# Solid_Sequencer.net
KiCad netlist of a schematic drawn in EAGLE
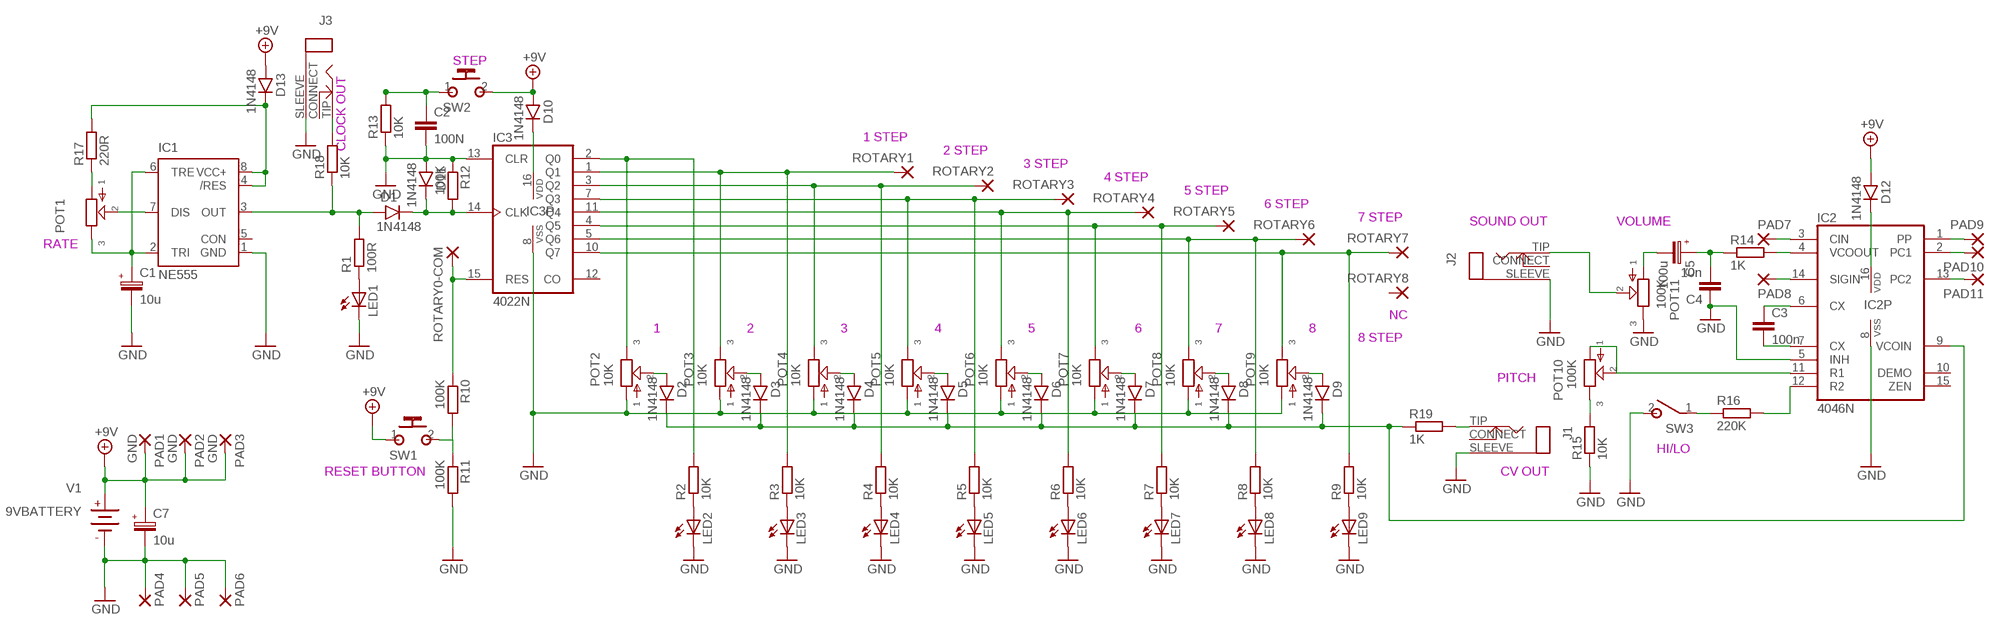
[diagram p0: schematic, sheet 1]

(export (version "E")
  (design (tool "Eeschema 10.0.6"))
  (components
    (comp (ref "C1")
      (value "10u")
      (footprint "eagle-import:050_020")
      (libsource (lib "eagle-import") (part "050-EU"))
    )
    (comp (ref "C2")
      (value "100N")
      (footprint "eagle-import:075X030_3")
      (libsource (lib "eagle-import") (part "075X0303"))
    )
    (comp (ref "C3")
      (value "100n")
      (footprint "eagle-import:075X030")
      (libsource (lib "eagle-import") (part "075X0302"))
    )
    (comp (ref "C4")
      (value "10n")
      (footprint "eagle-import:075X030")
      (libsource (lib "eagle-import") (part "075X0302"))
    )
    (comp (ref "C5")
      (value "100u")
      (footprint "eagle-import:050_020_1")
      (libsource (lib "eagle-import") (part "050-EU1"))
    )
    (comp (ref "C7")
      (value "10u")
      (footprint "eagle-import:050_020_1")
      (libsource (lib "eagle-import") (part "050-EU1"))
    )
    (comp (ref "D1")
      (value "1N4148")
      (footprint "eagle-import:DO35-3")
      (libsource (lib "eagle-import") (part "1N914.3"))
    )
    (comp (ref "D2")
      (value "1N4148")
      (footprint "eagle-import:DO35-3")
      (libsource (lib "eagle-import") (part "1N914.3"))
    )
    (comp (ref "D3")
      (value "1N4148")
      (footprint "eagle-import:DO35-3")
      (libsource (lib "eagle-import") (part "1N914.3"))
    )
    (comp (ref "D4")
      (value "1N4148")
      (footprint "eagle-import:DO35-3")
      (libsource (lib "eagle-import") (part "1N914.3"))
    )
    (comp (ref "D5")
      (value "1N4148")
      (footprint "eagle-import:DO35-3")
      (libsource (lib "eagle-import") (part "1N914.3"))
    )
    (comp (ref "D6")
      (value "1N4148")
      (footprint "eagle-import:DO35-3")
      (libsource (lib "eagle-import") (part "1N914.3"))
    )
    (comp (ref "D7")
      (value "1N4148")
      (footprint "eagle-import:DO35-3")
      (libsource (lib "eagle-import") (part "1N914.3"))
    )
    (comp (ref "D8")
      (value "1N4148")
      (footprint "eagle-import:DO35-3")
      (libsource (lib "eagle-import") (part "1N914.3"))
    )
    (comp (ref "D9")
      (value "1N4148")
      (footprint "eagle-import:DO35-3")
      (libsource (lib "eagle-import") (part "1N914.3"))
    )
    (comp (ref "D10")
      (value "1N4148")
      (footprint "eagle-import:DO35-3")
      (libsource (lib "eagle-import") (part "1N914.3"))
    )
    (comp (ref "D11")
      (value "1N4148")
      (footprint "eagle-import:DO35-3")
      (libsource (lib "eagle-import") (part "1N914.3"))
    )
    (comp (ref "D12")
      (value "1N4148")
      (footprint "eagle-import:DO35-3")
      (libsource (lib "eagle-import") (part "1N914.3"))
    )
    (comp (ref "D13")
      (value "1N4148")
      (footprint "eagle-import:DO35-3")
      (libsource (lib "eagle-import") (part "1N914.3"))
    )
    (comp (ref "IC1")
      (value "NE555")
      (footprint "eagle-import:DIL-08")
      (fields (field (name "MF") "Arrow Electronics") (field (name "MPN") "NE555N"))
      (libsource (lib "eagle-import") (part "NE555"))
    )
    (comp (ref "IC2")
      (value "4046N")
      (footprint "eagle-import:DIL16")
      (libsource (lib "eagle-import") (part "4046N"))
    )
    (comp (ref "IC3")
      (value "4022N")
      (footprint "eagle-import:DIL16")
      (libsource (lib "eagle-import") (part "4022N"))
    )
    (comp (ref "J1")
      (value "CLOSEDMONO")
      (footprint "eagle-import:CLOSED_MONO_JACK")
      (libsource (lib "eagle-import") (part "CLOSEDMONO"))
    )
    (comp (ref "J2")
      (value "CLOSEDMONO")
      (footprint "eagle-import:CLOSED_MONO_JACK")
      (libsource (lib "eagle-import") (part "CLOSEDMONO"))
    )
    (comp (ref "J3")
      (value "CLOSEDMONO")
      (footprint "eagle-import:CLOSED_MONO_JACK")
      (libsource (lib "eagle-import") (part "CLOSEDMONO"))
    )
    (comp (ref "LED1")
      (value "LED3MM")
      (footprint "eagle-import:LED3MM")
      (libsource (lib "eagle-import") (part "LED3MM"))
    )
    (comp (ref "LED2")
      (value "LED3MM")
      (footprint "eagle-import:LED3MM")
      (libsource (lib "eagle-import") (part "LED3MM"))
    )
    (comp (ref "LED3")
      (value "LED3MM")
      (footprint "eagle-import:LED3MM")
      (libsource (lib "eagle-import") (part "LED3MM"))
    )
    (comp (ref "LED4")
      (value "LED3MM")
      (footprint "eagle-import:LED3MM")
      (libsource (lib "eagle-import") (part "LED3MM"))
    )
    (comp (ref "LED5")
      (value "LED3MM")
      (footprint "eagle-import:LED3MM")
      (libsource (lib "eagle-import") (part "LED3MM"))
    )
    (comp (ref "LED6")
      (value "LED3MM")
      (footprint "eagle-import:LED3MM")
      (libsource (lib "eagle-import") (part "LED3MM"))
    )
    (comp (ref "LED7")
      (value "LED3MM")
      (footprint "eagle-import:LED3MM")
      (libsource (lib "eagle-import") (part "LED3MM"))
    )
    (comp (ref "LED8")
      (value "LED3MM")
      (footprint "eagle-import:LED3MM")
      (libsource (lib "eagle-import") (part "LED3MM"))
    )
    (comp (ref "LED9")
      (value "LED3MM")
      (footprint "eagle-import:LED3MM")
      (libsource (lib "eagle-import") (part "LED3MM"))
    )
    (comp (ref "PAD1")
      (value "GND")
      (footprint "eagle-import:2,15_1,0")
      (libsource (lib "eagle-import") (part "2,15/1,0"))
    )
    (comp (ref "PAD2")
      (value "GND")
      (footprint "eagle-import:2,15_1,0")
      (libsource (lib "eagle-import") (part "2,15/1,0"))
    )
    (comp (ref "PAD3")
      (value "GND")
      (footprint "eagle-import:2,15_1,0")
      (libsource (lib "eagle-import") (part "2,15/1,0"))
    )
    (comp (ref "PAD4")
      (value "2,15/1,0")
      (footprint "eagle-import:2,15_1,0")
      (libsource (lib "eagle-import") (part "2,15/1,0"))
    )
    (comp (ref "PAD5")
      (value "2,15/1,0")
      (footprint "eagle-import:2,15_1,0")
      (libsource (lib "eagle-import") (part "2,15/1,0"))
    )
    (comp (ref "PAD6")
      (value "2,15/1,0")
      (footprint "eagle-import:2,15_1,0")
      (libsource (lib "eagle-import") (part "2,15/1,0"))
    )
    (comp (ref "PAD7")
      (value "2,15/1,0")
      (footprint "eagle-import:2,15_1,0")
      (libsource (lib "eagle-import") (part "2,15/1,0"))
    )
    (comp (ref "PAD8")
      (value "2,15/1,0")
      (footprint "eagle-import:2,15_1,0")
      (libsource (lib "eagle-import") (part "2,15/1,0"))
    )
    (comp (ref "PAD9")
      (value "2,15/1,0")
      (footprint "eagle-import:2,15_1,0")
      (libsource (lib "eagle-import") (part "2,15/1,0"))
    )
    (comp (ref "PAD10")
      (value "2,15/1,0")
      (footprint "eagle-import:2,15_1,0")
      (libsource (lib "eagle-import") (part "2,15/1,0"))
    )
    (comp (ref "PAD11")
      (value "2,15/1,0")
      (footprint "eagle-import:2,15_1,0")
      (libsource (lib "eagle-import") (part "2,15/1,0"))
    )
    (comp (ref "POT1")
      (value "POT-EU")
      (footprint "eagle-import:POT")
      (libsource (lib "eagle-import") (part "POT-EU"))
    )
    (comp (ref "POT2")
      (value "10K")
      (footprint "eagle-import:POT")
      (libsource (lib "eagle-import") (part "POT-EU"))
    )
    (comp (ref "POT3")
      (value "10K")
      (footprint "eagle-import:POT")
      (libsource (lib "eagle-import") (part "POT-EU"))
    )
    (comp (ref "POT4")
      (value "10K")
      (footprint "eagle-import:POT")
      (libsource (lib "eagle-import") (part "POT-EU"))
    )
    (comp (ref "POT5")
      (value "10K")
      (footprint "eagle-import:POT")
      (libsource (lib "eagle-import") (part "POT-EU"))
    )
    (comp (ref "POT6")
      (value "10K")
      (footprint "eagle-import:POT")
      (libsource (lib "eagle-import") (part "POT-EU"))
    )
    (comp (ref "POT7")
      (value "10K")
      (footprint "eagle-import:POT")
      (libsource (lib "eagle-import") (part "POT-EU"))
    )
    (comp (ref "POT8")
      (value "10K")
      (footprint "eagle-import:POT")
      (libsource (lib "eagle-import") (part "POT-EU"))
    )
    (comp (ref "POT9")
      (value "10K")
      (footprint "eagle-import:POT")
      (libsource (lib "eagle-import") (part "POT-EU"))
    )
    (comp (ref "POT10")
      (value "100K")
      (footprint "eagle-import:POT")
      (libsource (lib "eagle-import") (part "POT-EU"))
    )
    (comp (ref "POT11")
      (value "100K")
      (footprint "eagle-import:POT")
      (libsource (lib "eagle-import") (part "POT-EU"))
    )
    (comp (ref "R1")
      (value "100R")
      (footprint "eagle-import:0207_7")
      (libsource (lib "eagle-import") (part "R-EU_0207/7"))
    )
    (comp (ref "R2")
      (value "10K")
      (footprint "eagle-import:0207_7")
      (libsource (lib "eagle-import") (part "R-EU_0207/7"))
    )
    (comp (ref "R3")
      (value "10K")
      (footprint "eagle-import:0207_7")
      (libsource (lib "eagle-import") (part "R-EU_0207/7"))
    )
    (comp (ref "R4")
      (value "10K")
      (footprint "eagle-import:0207_7")
      (libsource (lib "eagle-import") (part "R-EU_0207/7"))
    )
    (comp (ref "R5")
      (value "10K")
      (footprint "eagle-import:0207_7")
      (libsource (lib "eagle-import") (part "R-EU_0207/7"))
    )
    (comp (ref "R6")
      (value "10K")
      (footprint "eagle-import:0207_7")
      (libsource (lib "eagle-import") (part "R-EU_0207/7"))
    )
    (comp (ref "R7")
      (value "10K")
      (footprint "eagle-import:0207_7")
      (libsource (lib "eagle-import") (part "R-EU_0207/7"))
    )
    (comp (ref "R8")
      (value "10K")
      (footprint "eagle-import:0207_7")
      (libsource (lib "eagle-import") (part "R-EU_0207/7"))
    )
    (comp (ref "R9")
      (value "10K")
      (footprint "eagle-import:0207_7")
      (libsource (lib "eagle-import") (part "R-EU_0207/7"))
    )
    (comp (ref "R10")
      (value "100K")
      (footprint "eagle-import:0207_7")
      (libsource (lib "eagle-import") (part "R-EU_0207/7"))
    )
    (comp (ref "R11")
      (value "100K")
      (footprint "eagle-import:0207_7")
      (libsource (lib "eagle-import") (part "R-EU_0207/7"))
    )
    (comp (ref "R12")
      (value "100K")
      (footprint "eagle-import:0207_7")
      (libsource (lib "eagle-import") (part "R-EU_0207/7"))
    )
    (comp (ref "R13")
      (value "10K")
      (footprint "eagle-import:0207_7")
      (libsource (lib "eagle-import") (part "R-EU_0207/7"))
    )
    (comp (ref "R14")
      (value "1K")
      (footprint "eagle-import:0207_7")
      (libsource (lib "eagle-import") (part "R-EU_0207/7"))
    )
    (comp (ref "R15")
      (value "10K")
      (footprint "eagle-import:0207_7")
      (libsource (lib "eagle-import") (part "R-EU_0207/7"))
    )
    (comp (ref "R16")
      (value "220K")
      (footprint "eagle-import:0207_7")
      (libsource (lib "eagle-import") (part "R-EU_0207/7"))
    )
    (comp (ref "R17")
      (value "220R")
      (footprint "eagle-import:0207_7")
      (libsource (lib "eagle-import") (part "R-EU_0207/7"))
    )
    (comp (ref "R18")
      (value "10K")
      (footprint "eagle-import:0207_7")
      (libsource (lib "eagle-import") (part "R-EU_0207/7"))
    )
    (comp (ref "R19")
      (value "1K")
      (footprint "eagle-import:0207_7")
      (libsource (lib "eagle-import") (part "R-EU_0207/7"))
    )
    (comp (ref "ROTARY0-COM")
      (value "2,15/1,0")
      (footprint "eagle-import:2,15_1,0")
      (libsource (lib "eagle-import") (part "2,15/1,0"))
    )
    (comp (ref "ROTARY1")
      (value "2,15/1,0")
      (footprint "eagle-import:2,15_1,0")
      (libsource (lib "eagle-import") (part "2,15/1,0"))
    )
    (comp (ref "ROTARY2")
      (value "2,15/1,0")
      (footprint "eagle-import:2,15_1,0")
      (libsource (lib "eagle-import") (part "2,15/1,0"))
    )
    (comp (ref "ROTARY3")
      (value "2,15/1,0")
      (footprint "eagle-import:2,15_1,0")
      (libsource (lib "eagle-import") (part "2,15/1,0"))
    )
    (comp (ref "ROTARY4")
      (value "2,15/1,0")
      (footprint "eagle-import:2,15_1,0")
      (libsource (lib "eagle-import") (part "2,15/1,0"))
    )
    (comp (ref "ROTARY5")
      (value "2,15/1,0")
      (footprint "eagle-import:2,15_1,0")
      (libsource (lib "eagle-import") (part "2,15/1,0"))
    )
    (comp (ref "ROTARY6")
      (value "2,15/1,0")
      (footprint "eagle-import:2,15_1,0")
      (libsource (lib "eagle-import") (part "2,15/1,0"))
    )
    (comp (ref "ROTARY7")
      (value "2,15/1,0")
      (footprint "eagle-import:2,15_1,0")
      (libsource (lib "eagle-import") (part "2,15/1,0"))
    )
    (comp (ref "ROTARY8")
      (value "2,15/1,0")
      (footprint "eagle-import:2,15_1,0")
      (libsource (lib "eagle-import") (part "2,15/1,0"))
    )
    (comp (ref "SW1")
      (value "MOMENTARY")
      (footprint "eagle-import:SPST")
      (libsource (lib "eagle-import") (part "MOMENTARY"))
    )
    (comp (ref "SW2")
      (value "MOMENTARY")
      (footprint "eagle-import:SPST")
      (libsource (lib "eagle-import") (part "MOMENTARY"))
    )
    (comp (ref "SW3")
      (value "SPST")
      (footprint "eagle-import:SPST")
      (libsource (lib "eagle-import") (part "SPST"))
    )
    (comp (ref "V1")
      (value "9VBATTERY")
      (footprint "eagle-import:AB9V")
      (libsource (lib "eagle-import") (part "9VBATTERY"))
    )
  )
  (nets
    (net (code "1") (name "+9V") (class "Default")
      (node (ref "C7") (pin "+") (pinfunction "+_+") (pintype "passive"))
      (node (ref "D10") (pin "A") (pinfunction "A_A") (pintype "passive"))
      (node (ref "D12") (pin "A") (pinfunction "A_A") (pintype "passive"))
      (node (ref "D13") (pin "A") (pinfunction "A_A") (pintype "passive"))
      (node (ref "PAD1") (pin "1") (pinfunction "P_1") (pintype "passive"))
      (node (ref "PAD2") (pin "1") (pinfunction "P_1") (pintype "passive"))
      (node (ref "PAD3") (pin "1") (pinfunction "P_1") (pintype "passive"))
      (node (ref "SW1") (pin "1") (pinfunction "P_1") (pintype "passive"))
      (node (ref "SW2") (pin "2") (pinfunction "S_2") (pintype "passive"))
      (node (ref "V1") (pin "+") (pinfunction "+_+") (pintype "passive"))
    )
    (net (code "2") (name "GND") (class "Default")
      (node (ref "C1") (pin "-") (pinfunction "-_-") (pintype "passive"))
      (node (ref "C2") (pin "2") (pinfunction "2_2") (pintype "passive"))
      (node (ref "C4") (pin "1") (pinfunction "1_1") (pintype "passive"))
      (node (ref "C7") (pin "-") (pinfunction "-_-") (pintype "passive"))
      (node (ref "D11") (pin "A") (pinfunction "A_A") (pintype "passive"))
      (node (ref "IC1") (pin "1") (pinfunction "GND_1") (pintype "power_in"))
      (node (ref "IC2") (pin "5") (pinfunction "INH_5") (pintype "input"))
      (node (ref "IC2") (pin "8") (pinfunction "VSS_8") (pintype "power_in"))
      (node (ref "IC3") (pin "13") (pinfunction "CLR_13") (pintype "input"))
      (node (ref "IC3") (pin "8") (pinfunction "VSS_8") (pintype "power_in"))
      (node (ref "J1") (pin "SLEEVE") (pinfunction "RING_SLEEVE") (pintype "passive"))
      (node (ref "J2") (pin "SLEEVE") (pinfunction "RING_SLEEVE") (pintype "passive"))
      (node (ref "J3") (pin "SLEEVE") (pinfunction "RING_SLEEVE") (pintype "passive"))
      (node (ref "LED1") (pin "K") (pinfunction "C_K") (pintype "passive"))
      (node (ref "LED2") (pin "K") (pinfunction "C_K") (pintype "passive"))
      (node (ref "LED3") (pin "K") (pinfunction "C_K") (pintype "passive"))
      (node (ref "LED4") (pin "K") (pinfunction "C_K") (pintype "passive"))
      (node (ref "LED5") (pin "K") (pinfunction "C_K") (pintype "passive"))
      (node (ref "LED6") (pin "K") (pinfunction "C_K") (pintype "passive"))
      (node (ref "LED7") (pin "K") (pinfunction "C_K") (pintype "passive"))
      (node (ref "LED8") (pin "K") (pinfunction "C_K") (pintype "passive"))
      (node (ref "LED9") (pin "K") (pinfunction "C_K") (pintype "passive"))
      (node (ref "PAD4") (pin "1") (pinfunction "P_1") (pintype "passive"))
      (node (ref "PAD5") (pin "1") (pinfunction "P_1") (pintype "passive"))
      (node (ref "PAD6") (pin "1") (pinfunction "P_1") (pintype "passive"))
      (node (ref "POT11") (pin "3") (pinfunction "3_3") (pintype "passive"))
      (node (ref "POT2") (pin "1") (pinfunction "1_1") (pintype "passive"))
      (node (ref "POT3") (pin "1") (pinfunction "1_1") (pintype "passive"))
      (node (ref "POT4") (pin "1") (pinfunction "1_1") (pintype "passive"))
      (node (ref "POT5") (pin "1") (pinfunction "1_1") (pintype "passive"))
      (node (ref "POT6") (pin "1") (pinfunction "1_1") (pintype "passive"))
      (node (ref "POT7") (pin "1") (pinfunction "1_1") (pintype "passive"))
      (node (ref "POT8") (pin "1") (pinfunction "1_1") (pintype "passive"))
      (node (ref "POT9") (pin "1") (pinfunction "1_1") (pintype "passive"))
      (node (ref "R11") (pin "2") (pinfunction "2_2") (pintype "passive"))
      (node (ref "R12") (pin "1") (pinfunction "1_1") (pintype "passive"))
      (node (ref "R13") (pin "1") (pinfunction "1_1") (pintype "passive"))
      (node (ref "R15") (pin "1") (pinfunction "1_1") (pintype "passive"))
      (node (ref "SW3") (pin "2") (pinfunction "S_2") (pintype "passive"))
      (node (ref "V1") (pin "-") (pinfunction "-_-") (pintype "passive"))
    )
    (net (code "3") (name "Net-(C3-Pad1)") (class "Default")
      (node (ref "C3") (pin "1") (pinfunction "1_1") (pintype "passive"))
      (node (ref "IC2") (pin "6") (pinfunction "CX_6") (pintype "input"))
    )
    (net (code "4") (name "Net-(C3-Pad2)") (class "Default")
      (node (ref "C3") (pin "2") (pinfunction "2_2") (pintype "passive"))
      (node (ref "IC2") (pin "7") (pinfunction "CX_7") (pintype "input"))
    )
    (net (code "5") (name "Net-(C4-Pad2)") (class "Default")
      (node (ref "C4") (pin "2") (pinfunction "2_2") (pintype "passive"))
      (node (ref "C5") (pin "+") (pinfunction "+_+") (pintype "passive"))
      (node (ref "R14") (pin "1") (pinfunction "1_1") (pintype "passive"))
    )
    (net (code "6") (name "Net-(C5-Pad-)") (class "Default")
      (node (ref "C5") (pin "-") (pinfunction "-_-") (pintype "passive"))
      (node (ref "POT11") (pin "1") (pinfunction "1_1") (pintype "passive"))
    )
    (net (code "7") (name "Net-(D2-PadA)") (class "Default")
      (node (ref "D2") (pin "A") (pinfunction "A_A") (pintype "passive"))
      (node (ref "POT2") (pin "2") (pinfunction "2_2") (pintype "passive"))
    )
    (net (code "8") (name "Net-(D3-PadA)") (class "Default")
      (node (ref "D3") (pin "A") (pinfunction "A_A") (pintype "passive"))
      (node (ref "POT3") (pin "2") (pinfunction "2_2") (pintype "passive"))
    )
    (net (code "9") (name "Net-(D4-PadA)") (class "Default")
      (node (ref "D4") (pin "A") (pinfunction "A_A") (pintype "passive"))
      (node (ref "POT4") (pin "2") (pinfunction "2_2") (pintype "passive"))
    )
    (net (code "10") (name "Net-(D5-PadA)") (class "Default")
      (node (ref "D5") (pin "A") (pinfunction "A_A") (pintype "passive"))
      (node (ref "POT5") (pin "2") (pinfunction "2_2") (pintype "passive"))
    )
    (net (code "11") (name "Net-(D6-PadA)") (class "Default")
      (node (ref "D6") (pin "A") (pinfunction "A_A") (pintype "passive"))
      (node (ref "POT6") (pin "2") (pinfunction "2_2") (pintype "passive"))
    )
    (net (code "12") (name "Net-(D7-PadA)") (class "Default")
      (node (ref "D7") (pin "A") (pinfunction "A_A") (pintype "passive"))
      (node (ref "POT7") (pin "2") (pinfunction "2_2") (pintype "passive"))
    )
    (net (code "13") (name "Net-(D8-PadA)") (class "Default")
      (node (ref "D8") (pin "A") (pinfunction "A_A") (pintype "passive"))
      (node (ref "POT8") (pin "2") (pinfunction "2_2") (pintype "passive"))
    )
    (net (code "14") (name "Net-(D9-PadA)") (class "Default")
      (node (ref "D9") (pin "A") (pinfunction "A_A") (pintype "passive"))
      (node (ref "POT9") (pin "2") (pinfunction "2_2") (pintype "passive"))
    )
    (net (code "15") (name "Net-(IC1-DIS)") (class "Default")
      (node (ref "IC1") (pin "7") (pinfunction "DIS_7") (pintype "input"))
      (node (ref "POT1") (pin "2") (pinfunction "2_2") (pintype "passive"))
    )
    (net (code "16") (name "Net-(IC1-OUT)") (class "Default")
      (node (ref "D1") (pin "A") (pinfunction "A_A") (pintype "passive"))
      (node (ref "IC1") (pin "3") (pinfunction "OUT_3") (pintype "output"))
      (node (ref "R1") (pin "2") (pinfunction "2_2") (pintype "passive"))
      (node (ref "R18") (pin "1") (pinfunction "1_1") (pintype "passive"))
    )
    (net (code "17") (name "Net-(IC1-TRE)") (class "Default")
      (node (ref "C1") (pin "+") (pinfunction "+_+") (pintype "passive"))
      (node (ref "IC1") (pin "2") (pinfunction "TRI_2") (pintype "input"))
      (node (ref "IC1") (pin "6") (pinfunction "TRE_6") (pintype "input"))
      (node (ref "POT1") (pin "3") (pinfunction "3_3") (pintype "passive"))
    )
    (net (code "18") (name "Net-(IC1-VCC+)") (class "Default")
      (node (ref "D13") (pin "C") (pinfunction "C_C") (pintype "passive"))
      (node (ref "IC1") (pin "4") (pinfunction "/RES_4") (pintype "input"))
      (node (ref "IC1") (pin "8") (pinfunction "VCC+_8") (pintype "power_in"))
      (node (ref "R17") (pin "2") (pinfunction "2_2") (pintype "passive"))
    )
    (net (code "19") (name "Net-(IC2A-CIN)") (class "Default")
      (node (ref "IC2") (pin "3") (pinfunction "CIN_3") (pintype "input"))
      (node (ref "PAD7") (pin "1") (pinfunction "P_1") (pintype "passive"))
    )
    (net (code "20") (name "Net-(IC2A-PC1)") (class "Default")
      (node (ref "IC2") (pin "2") (pinfunction "PC1_2") (pintype "output"))
      (node (ref "PAD10") (pin "1") (pinfunction "P_1") (pintype "passive"))
    )
    (net (code "21") (name "Net-(IC2A-PC2)") (class "Default")
      (node (ref "IC2") (pin "13") (pinfunction "PC2_13") (pintype "output"))
      (node (ref "PAD11") (pin "1") (pinfunction "P_1") (pintype "passive"))
    )
    (net (code "22") (name "Net-(IC2A-PP)") (class "Default")
      (node (ref "IC2") (pin "1") (pinfunction "PP_1") (pintype "output"))
      (node (ref "PAD9") (pin "1") (pinfunction "P_1") (pintype "passive"))
    )
    (net (code "23") (name "Net-(IC2A-R1)") (class "Default")
      (node (ref "IC2") (pin "11") (pinfunction "R1_11") (pintype "input"))
      (node (ref "POT10") (pin "1") (pinfunction "1_1") (pintype "passive"))
      (node (ref "POT10") (pin "2") (pinfunction "2_2") (pintype "passive"))
    )
    (net (code "24") (name "Net-(IC2A-R2)") (class "Default")
      (node (ref "IC2") (pin "12") (pinfunction "R2_12") (pintype "input"))
      (node (ref "R16") (pin "2") (pinfunction "2_2") (pintype "passive"))
    )
    (net (code "25") (name "Net-(IC2A-SIGIN)") (class "Default")
      (node (ref "IC2") (pin "14") (pinfunction "SIGIN_14") (pintype "input"))
      (node (ref "PAD8") (pin "1") (pinfunction "P_1") (pintype "passive"))
    )
    (net (code "26") (name "Net-(IC2A-VCOIN)") (class "Default")
      (node (ref "D2") (pin "C") (pinfunction "C_C") (pintype "passive"))
      (node (ref "D3") (pin "C") (pinfunction "C_C") (pintype "passive"))
      (node (ref "D4") (pin "C") (pinfunction "C_C") (pintype "passive"))
      (node (ref "D5") (pin "C") (pinfunction "C_C") (pintype "passive"))
      (node (ref "D6") (pin "C") (pinfunction "C_C") (pintype "passive"))
      (node (ref "D7") (pin "C") (pinfunction "C_C") (pintype "passive"))
      (node (ref "D8") (pin "C") (pinfunction "C_C") (pintype "passive"))
      (node (ref "D9") (pin "C") (pinfunction "C_C") (pintype "passive"))
      (node (ref "IC2") (pin "9") (pinfunction "VCOIN_9") (pintype "input"))
      (node (ref "R19") (pin "1") (pinfunction "1_1") (pintype "passive"))
    )
    (net (code "27") (name "Net-(IC2A-VCOOUT)") (class "Default")
      (node (ref "IC2") (pin "4") (pinfunction "VCOOUT_4") (pintype "output"))
      (node (ref "R14") (pin "2") (pinfunction "2_2") (pintype "passive"))
    )
    (net (code "28") (name "Net-(IC2B-VDD)") (class "Default")
      (node (ref "D12") (pin "C") (pinfunction "C_C") (pintype "passive"))
      (node (ref "IC2") (pin "16") (pinfunction "VDD_16") (pintype "power_in"))
    )
    (net (code "29") (name "Net-(IC3A-CLK)") (class "Default")
      (node (ref "D1") (pin "C") (pinfunction "C_C") (pintype "passive"))
      (node (ref "D11") (pin "C") (pinfunction "C_C") (pintype "passive"))
      (node (ref "IC3") (pin "14") (pinfunction "CLK_14") (pintype "input"))
      (node (ref "R12") (pin "2") (pinfunction "2_2") (pintype "passive"))
    )
    (net (code "30") (name "Net-(IC3A-Q0)") (class "Default")
      (node (ref "IC3") (pin "2") (pinfunction "Q0_2") (pintype "output"))
      (node (ref "POT2") (pin "3") (pinfunction "3_3") (pintype "passive"))
      (node (ref "R2") (pin "2") (pinfunction "2_2") (pintype "passive"))
    )
    (net (code "31") (name "Net-(IC3A-Q1)") (class "Default")
      (node (ref "IC3") (pin "1") (pinfunction "Q1_1") (pintype "output"))
      (node (ref "POT3") (pin "3") (pinfunction "3_3") (pintype "passive"))
      (node (ref "R3") (pin "2") (pinfunction "2_2") (pintype "passive"))
      (node (ref "ROTARY1") (pin "1") (pinfunction "P_1") (pintype "passive"))
    )
    (net (code "32") (name "Net-(IC3A-Q2)") (class "Default")
      (node (ref "IC3") (pin "3") (pinfunction "Q2_3") (pintype "output"))
      (node (ref "POT4") (pin "3") (pinfunction "3_3") (pintype "passive"))
      (node (ref "R4") (pin "2") (pinfunction "2_2") (pintype "passive"))
      (node (ref "ROTARY2") (pin "1") (pinfunction "P_1") (pintype "passive"))
    )
    (net (code "33") (name "Net-(IC3A-Q3)") (class "Default")
      (node (ref "IC3") (pin "7") (pinfunction "Q3_7") (pintype "output"))
      (node (ref "POT5") (pin "3") (pinfunction "3_3") (pintype "passive"))
      (node (ref "R5") (pin "2") (pinfunction "2_2") (pintype "passive"))
      (node (ref "ROTARY3") (pin "1") (pinfunction "P_1") (pintype "passive"))
    )
    (net (code "34") (name "Net-(IC3A-Q4)") (class "Default")
      (node (ref "IC3") (pin "11") (pinfunction "Q4_11") (pintype "output"))
      (node (ref "POT6") (pin "3") (pinfunction "3_3") (pintype "passive"))
      (node (ref "R6") (pin "2") (pinfunction "2_2") (pintype "passive"))
      (node (ref "ROTARY4") (pin "1") (pinfunction "P_1") (pintype "passive"))
    )
    (net (code "35") (name "Net-(IC3A-Q5)") (class "Default")
      (node (ref "IC3") (pin "4") (pinfunction "Q5_4") (pintype "output"))
      (node (ref "POT7") (pin "3") (pinfunction "3_3") (pintype "passive"))
      (node (ref "R7") (pin "2") (pinfunction "2_2") (pintype "passive"))
      (node (ref "ROTARY5") (pin "1") (pinfunction "P_1") (pintype "passive"))
    )
    (net (code "36") (name "Net-(IC3A-Q6)") (class "Default")
      (node (ref "IC3") (pin "5") (pinfunction "Q6_5") (pintype "output"))
      (node (ref "POT8") (pin "3") (pinfunction "3_3") (pintype "passive"))
      (node (ref "R8") (pin "2") (pinfunction "2_2") (pintype "passive"))
      (node (ref "ROTARY6") (pin "1") (pinfunction "P_1") (pintype "passive"))
    )
    (net (code "37") (name "Net-(IC3A-Q7)") (class "Default")
      (node (ref "IC3") (pin "10") (pinfunction "Q7_10") (pintype "output"))
      (node (ref "POT9") (pin "3") (pinfunction "3_3") (pintype "passive"))
      (node (ref "R9") (pin "2") (pinfunction "2_2") (pintype "passive"))
      (node (ref "ROTARY7") (pin "1") (pinfunction "P_1") (pintype "passive"))
    )
    (net (code "38") (name "Net-(IC3A-RES)") (class "Default")
      (node (ref "IC3") (pin "15") (pinfunction "RES_15") (pintype "input"))
      (node (ref "R10") (pin "1") (pinfunction "1_1") (pintype "passive"))
      (node (ref "ROTARY0-COM") (pin "1") (pinfunction "P_1") (pintype "passive"))
    )
    (net (code "39") (name "Net-(IC3B-VDD)") (class "Default")
      (node (ref "D10") (pin "C") (pinfunction "C_C") (pintype "passive"))
      (node (ref "IC3") (pin "16") (pinfunction "VDD_16") (pintype "power_in"))
    )
    (net (code "40") (name "Net-(J1-PadTIP)") (class "Default")
      (node (ref "J1") (pin "TIP") (pinfunction "TIP_TIP") (pintype "passive"))
      (node (ref "R19") (pin "2") (pinfunction "2_2") (pintype "passive"))
    )
    (net (code "41") (name "Net-(J2-PadTIP)") (class "Default")
      (node (ref "J2") (pin "TIP") (pinfunction "TIP_TIP") (pintype "passive"))
      (node (ref "POT11") (pin "2") (pinfunction "2_2") (pintype "passive"))
    )
    (net (code "42") (name "Net-(J3-PadTIP)") (class "Default")
      (node (ref "J3") (pin "TIP") (pinfunction "TIP_TIP") (pintype "passive"))
      (node (ref "R18") (pin "2") (pinfunction "2_2") (pintype "passive"))
    )
    (net (code "43") (name "Net-(LED1-PadA)") (class "Default")
      (node (ref "LED1") (pin "A") (pinfunction "A_A") (pintype "passive"))
      (node (ref "R1") (pin "1") (pinfunction "1_1") (pintype "passive"))
    )
    (net (code "44") (name "Net-(LED2-PadA)") (class "Default")
      (node (ref "LED2") (pin "A") (pinfunction "A_A") (pintype "passive"))
      (node (ref "R2") (pin "1") (pinfunction "1_1") (pintype "passive"))
    )
    (net (code "45") (name "Net-(LED3-PadA)") (class "Default")
      (node (ref "LED3") (pin "A") (pinfunction "A_A") (pintype "passive"))
      (node (ref "R3") (pin "1") (pinfunction "1_1") (pintype "passive"))
    )
    (net (code "46") (name "Net-(LED4-PadA)") (class "Default")
      (node (ref "LED4") (pin "A") (pinfunction "A_A") (pintype "passive"))
      (node (ref "R4") (pin "1") (pinfunction "1_1") (pintype "passive"))
    )
    (net (code "47") (name "Net-(LED5-PadA)") (class "Default")
      (node (ref "LED5") (pin "A") (pinfunction "A_A") (pintype "passive"))
      (node (ref "R5") (pin "1") (pinfunction "1_1") (pintype "passive"))
    )
    (net (code "48") (name "Net-(LED6-PadA)") (class "Default")
      (node (ref "LED6") (pin "A") (pinfunction "A_A") (pintype "passive"))
      (node (ref "R6") (pin "1") (pinfunction "1_1") (pintype "passive"))
    )
    (net (code "49") (name "Net-(LED7-PadA)") (class "Default")
      (node (ref "LED7") (pin "A") (pinfunction "A_A") (pintype "passive"))
      (node (ref "R7") (pin "1") (pinfunction "1_1") (pintype "passive"))
    )
    (net (code "50") (name "Net-(LED8-PadA)") (class "Default")
      (node (ref "LED8") (pin "A") (pinfunction "A_A") (pintype "passive"))
      (node (ref "R8") (pin "1") (pinfunction "1_1") (pintype "passive"))
    )
    (net (code "51") (name "Net-(LED9-PadA)") (class "Default")
      (node (ref "LED9") (pin "A") (pinfunction "A_A") (pintype "passive"))
      (node (ref "R9") (pin "1") (pinfunction "1_1") (pintype "passive"))
    )
    (net (code "52") (name "Net-(POT1-Pad1)") (class "Default")
      (node (ref "POT1") (pin "1") (pinfunction "1_1") (pintype "passive"))
      (node (ref "R17") (pin "1") (pinfunction "1_1") (pintype "passive"))
    )
    (net (code "53") (name "Net-(POT10-Pad3)") (class "Default")
      (node (ref "POT10") (pin "3") (pinfunction "3_3") (pintype "passive"))
      (node (ref "R15") (pin "2") (pinfunction "2_2") (pintype "passive"))
    )
    (net (code "54") (name "Net-(SW1-S)") (class "Default")
      (node (ref "R10") (pin "2") (pinfunction "2_2") (pintype "passive"))
      (node (ref "R11") (pin "1") (pinfunction "1_1") (pintype "passive"))
      (node (ref "SW1") (pin "2") (pinfunction "S_2") (pintype "passive"))
    )
    (net (code "55") (name "Net-(SW2-P)") (class "Default")
      (node (ref "C2") (pin "1") (pinfunction "1_1") (pintype "passive"))
      (node (ref "R13") (pin "2") (pinfunction "2_2") (pintype "passive"))
      (node (ref "SW2") (pin "1") (pinfunction "P_1") (pintype "passive"))
    )
    (net (code "56") (name "Net-(SW3-P)") (class "Default")
      (node (ref "R16") (pin "1") (pinfunction "1_1") (pintype "passive"))
      (node (ref "SW3") (pin "1") (pinfunction "P_1") (pintype "passive"))
    )
    (net (code "57") (name "unconnected-(IC1-CON-Pad5)") (class "Default")
      (node (ref "IC1") (pin "5") (pinfunction "CON_5") (pintype "input"))
    )
    (net (code "58") (name "unconnected-(IC2A-DEMO-Pad10)") (class "Default")
      (node (ref "IC2") (pin "10") (pinfunction "DEMO_10") (pintype "output"))
    )
    (net (code "59") (name "unconnected-(IC2A-ZEN-Pad15)") (class "Default")
      (node (ref "IC2") (pin "15") (pinfunction "ZEN_15") (pintype "input"))
    )
    (net (code "60") (name "unconnected-(IC3A-CO-Pad12)") (class "Default")
      (node (ref "IC3") (pin "12") (pinfunction "CO_12") (pintype "output"))
    )
    (net (code "61") (name "unconnected-(J1-PadCONNECT)") (class "Default")
      (node (ref "J1") (pin "CONNECT") (pinfunction "CONNECT_CONNECT") (pintype "passive"))
    )
    (net (code "62") (name "unconnected-(J2-PadCONNECT)") (class "Default")
      (node (ref "J2") (pin "CONNECT") (pinfunction "CONNECT_CONNECT") (pintype "passive"))
    )
    (net (code "63") (name "unconnected-(J3-PadCONNECT)") (class "Default")
      (node (ref "J3") (pin "CONNECT") (pinfunction "CONNECT_CONNECT") (pintype "passive"))
    )
    (net (code "64") (name "unconnected-(ROTARY8-P-Pad1)") (class "Default")
      (node (ref "ROTARY8") (pin "1") (pinfunction "P_1") (pintype "passive"))
    )
  )
)
